# design.net
KiCad netlist of a schematic drawn in Altium Designer
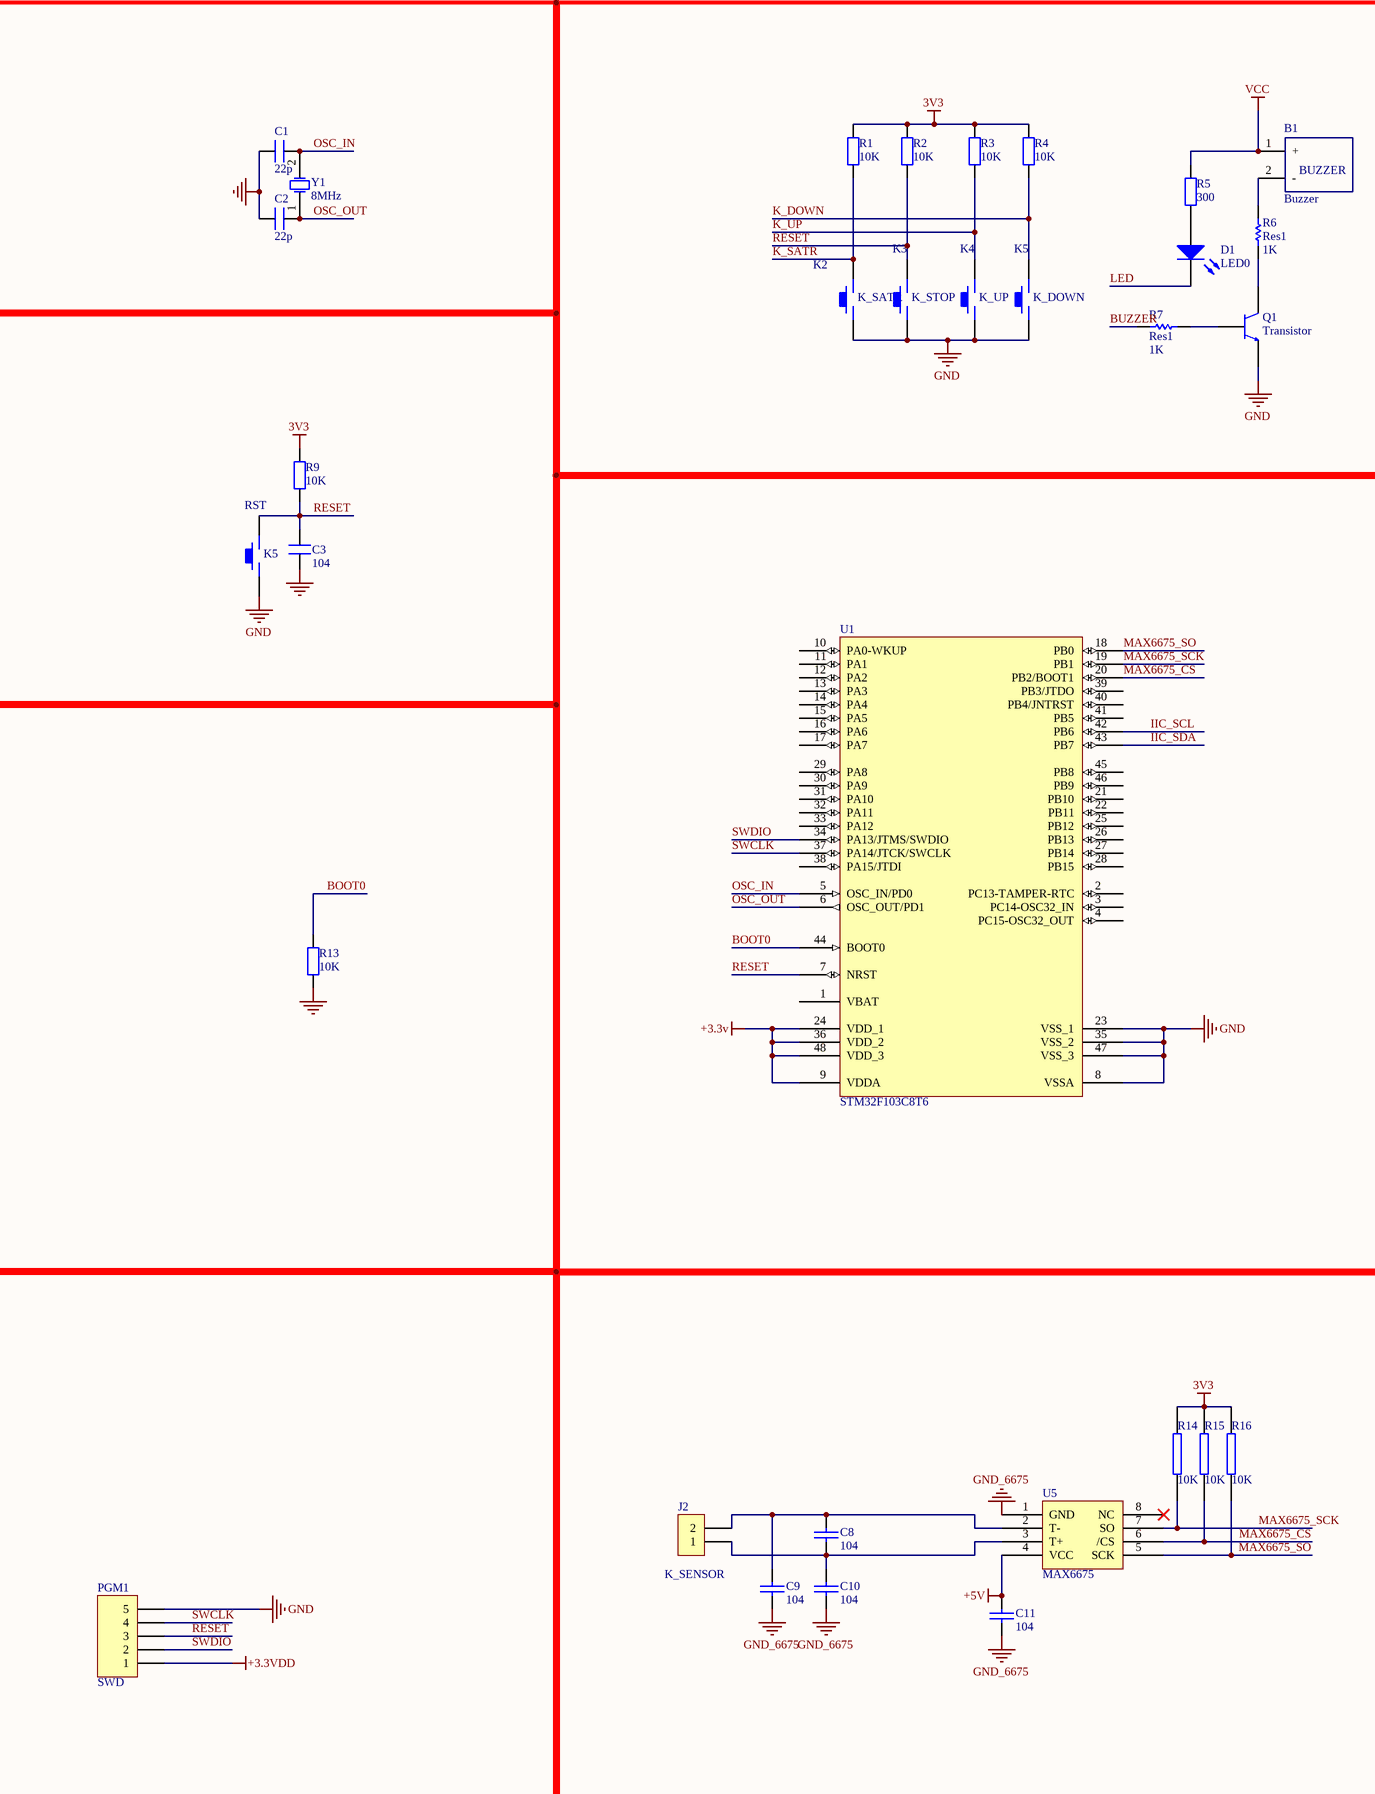
[diagram p0: 原理图.SchDoc, left]
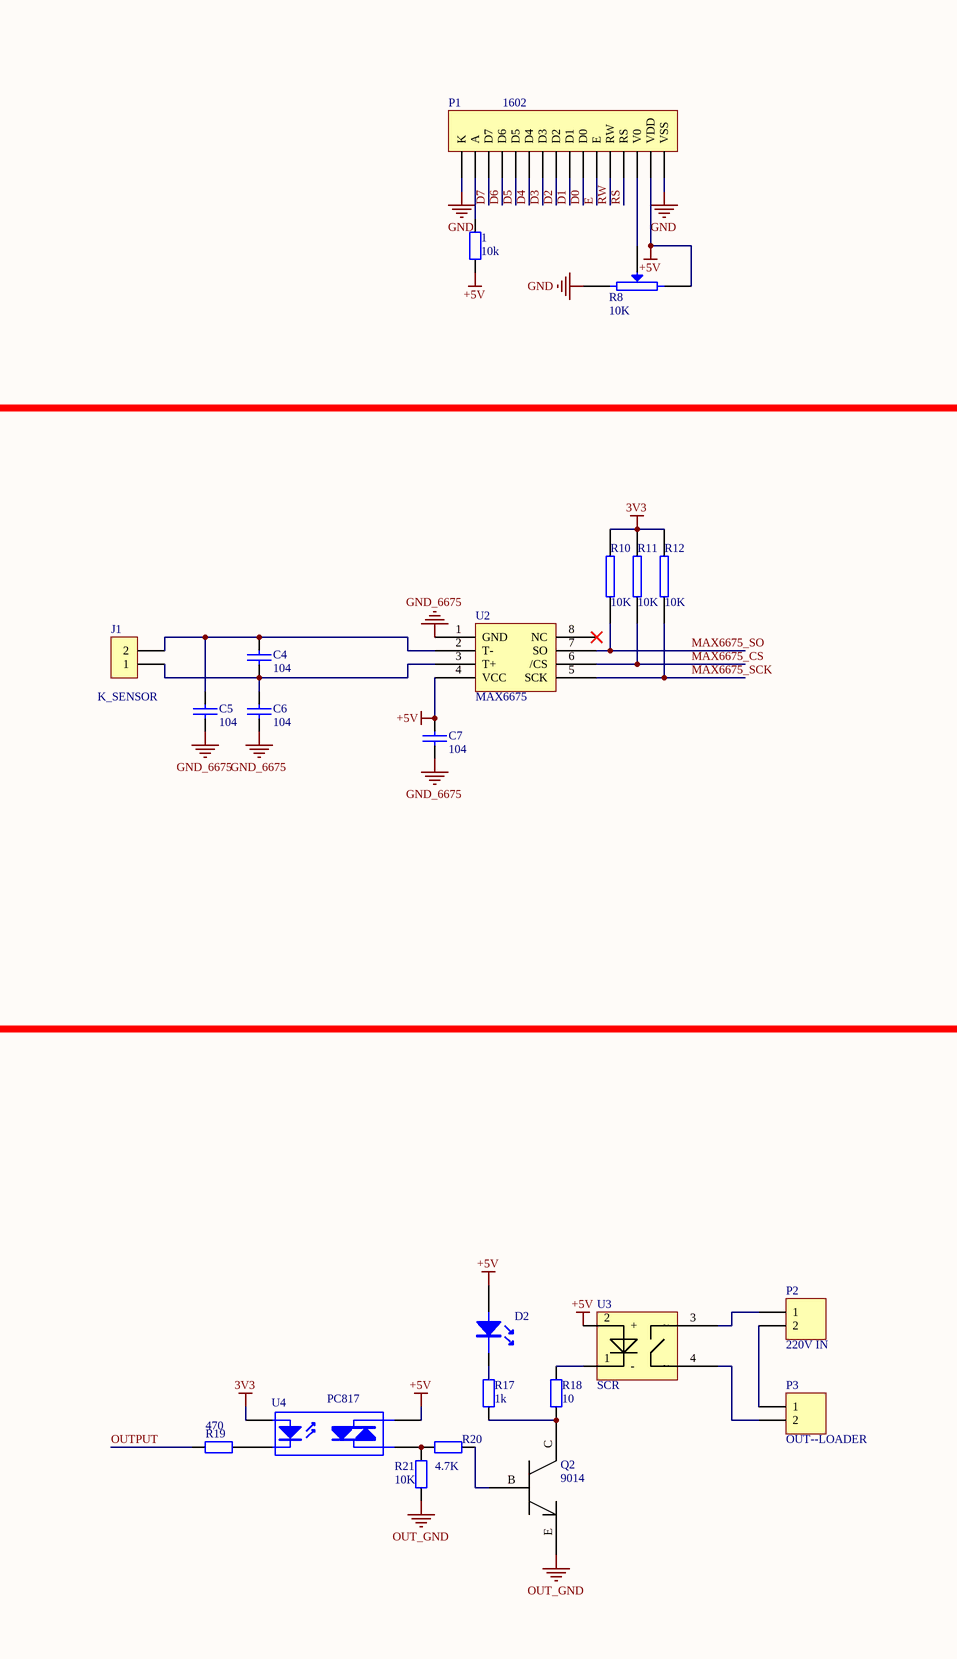
[diagram p1: 原理图.SchDoc, right]

(export (version "E")
  (design (tool "Eeschema 10.0.6"))
  (components
    (comp (ref "1")
      (value "10k")
      (footprint "AXIAL-0.4")
      (description "Resistor")
      (fields (field (name "PUBLISHER") "Altium Limited"))
      (libsource (lib "Miscellaneous Devices") (part "Res2"))
    )
    (comp (ref "B1") (value "Buzzer") (footprint "BUZZER") (libsource (lib "Second Version") (part "Buzzer")))
    (comp (ref "C1") (value "22p") (footprint "1206") (libsource (lib "MiniSTM32 V3.0封装库") (part "C")))
    (comp (ref "C2") (value "22p") (footprint "1206") (libsource (lib "MiniSTM32 V3.0封装库") (part "C")))
    (comp (ref "C3") (value "104") (footprint "1206") (libsource (lib "MiniSTM32 V3.0封装库") (part "C")))
    (comp (ref "C4")
      (value "104")
      (footprint "1206")
      (description "Capacitor")
      (libsource (lib "电容") (part "普通电容"))
    )
    (comp (ref "C5")
      (value "104")
      (footprint "1206")
      (description "Capacitor")
      (libsource (lib "电容") (part "普通电容"))
    )
    (comp (ref "C6")
      (value "104")
      (footprint "1206")
      (description "Capacitor")
      (libsource (lib "电容") (part "普通电容"))
    )
    (comp (ref "C7")
      (value "104")
      (footprint "1206")
      (description "Capacitor")
      (libsource (lib "电容") (part "普通电容"))
    )
    (comp (ref "C8")
      (value "104")
      (footprint "1206")
      (description "Capacitor")
      (libsource (lib "电容") (part "普通电容"))
    )
    (comp (ref "C9")
      (value "104")
      (footprint "1206")
      (description "Capacitor")
      (libsource (lib "电容") (part "普通电容"))
    )
    (comp (ref "C10")
      (value "104")
      (footprint "1206")
      (description "Capacitor")
      (libsource (lib "电容") (part "普通电容"))
    )
    (comp (ref "C11")
      (value "104")
      (footprint "1206")
      (description "Capacitor")
      (libsource (lib "电容") (part "普通电容"))
    )
    (comp (ref "D1")
      (value "LED0")
      (footprint "LED-0")
      (description "Typical INFRARED GaAs LED")
      (fields (field (name "PUBLISHER") "Altium Limited"))
      (libsource (lib "Miscellaneous Devices") (part "LED0"))
    )
    (comp (ref "D2") (value "~") (footprint "李建国1:LED") (libsource (lib "二极管") (part "发光二极管")))
    (comp (ref "J1")
      (value "K_SENSOR")
      (footprint "OUT_CJ")
      (description "Connector")
      (libsource (lib "Miscellaneous Devices") (part "CON2"))
    )
    (comp (ref "J2")
      (value "K_SENSOR")
      (footprint "OUT_CJ")
      (description "Connector")
      (libsource (lib "Miscellaneous Devices") (part "CON2"))
    )
    (comp (ref "K5") (value "RST") (footprint "KEY_M") (libsource (lib "底板封装库") (part "KEY_M")))
    (comp (ref "K_DOWN") (value "K5") (footprint "KEY_M") (libsource (lib "底板封装库") (part "KEY_M")))
    (comp (ref "K_SATR") (value "K2") (footprint "KEY_M") (libsource (lib "底板封装库") (part "KEY_M")))
    (comp (ref "K_STOP") (value "K3") (footprint "KEY_M") (libsource (lib "底板封装库") (part "KEY_M")))
    (comp (ref "K_UP") (value "K4") (footprint "KEY_M") (libsource (lib "底板封装库") (part "KEY_M")))
    (comp (ref "P1")
      (value "1602")
      (footprint "HDR1X16")
      (description "Header, 16-Pin")
      (fields (field (name "PUBLISHER") "Altium Limited"))
      (libsource (lib "Miscellaneous Connectors") (part "Header 16"))
    )
    (comp (ref "P2")
      (value "220V IN")
      (footprint "OUT_CJ")
      (description "Header, 2-Pin")
      (fields (field (name "PUBLISHER") "Altium Limited"))
      (libsource (lib "Miscellaneous Connectors") (part "Header 2"))
    )
    (comp (ref "P3")
      (value "OUT--LOADER")
      (footprint "OUT_CJ")
      (description "Header, 2-Pin")
      (fields (field (name "PUBLISHER") "Altium Limited"))
      (libsource (lib "Miscellaneous Connectors") (part "Header 2"))
    )
    (comp (ref "PGM1")
      (value "SWD")
      (footprint "HX2.54-5p")
      (description "Header, 5-Pin")
      (fields (field (name "PUBLISHER") "Altium Limited"))
      (libsource (lib "Miscellaneous Connectors") (part "Header 5"))
    )
    (comp (ref "Q1")
      (value "Transistor")
      (footprint "SOT23_TR")
      (libsource (lib "First Version") (part "NPN_Transistor_SOT23"))
    )
    (comp (ref "Q2") (value "9014") (footprint "9014") (libsource (lib "陈志伟2") (part "9014")))
    (comp (ref "R1")
      (value "10K")
      (footprint "1206")
      (description "Resistor")
      (fields (field (name "PUBLISHER") "Altium Limited"))
      (libsource (lib "") (part "Res2_2"))
    )
    (comp (ref "R2")
      (value "10K")
      (footprint "1206")
      (description "Resistor")
      (fields (field (name "PUBLISHER") "Altium Limited"))
      (libsource (lib "") (part "Res2_2"))
    )
    (comp (ref "R3")
      (value "10K")
      (footprint "1206")
      (description "Resistor")
      (fields (field (name "PUBLISHER") "Altium Limited"))
      (libsource (lib "") (part "Res2_2"))
    )
    (comp (ref "R4")
      (value "10K")
      (footprint "1206")
      (description "Resistor")
      (fields (field (name "PUBLISHER") "Altium Limited"))
      (libsource (lib "") (part "Res2_2"))
    )
    (comp (ref "R5")
      (value "300")
      (footprint "AXIAL-0.4")
      (description "Resistor")
      (fields (field (name "PUBLISHER") "Altium Limited"))
      (libsource (lib "Miscellaneous Devices") (part "Res2"))
    )
    (comp (ref "R6")
      (value "Res1")
      (footprint "SMD0805_RES")
      (description "Resistor")
      (fields (field (name "ALTIUM_VALUE") "1K") (field (name "PUBLISHER") "Altium Limited"))
      (libsource (lib "Miscellaneous Devices") (part "Res1"))
    )
    (comp (ref "R7")
      (value "Res1")
      (footprint "SMD0805_RES")
      (description "Resistor")
      (fields (field (name "ALTIUM_VALUE") "1K") (field (name "PUBLISHER") "Altium Limited"))
      (libsource (lib "Miscellaneous Devices") (part "Res1"))
    )
    (comp (ref "R8")
      (value "10K")
      (footprint "VR")
      (description "Potentiometer")
      (libsource (lib "电阻") (part "RESVR"))
    )
    (comp (ref "R9")
      (value "10K")
      (footprint "1206")
      (description "Resistor")
      (fields (field (name "PUBLISHER") "Altium Limited"))
      (libsource (lib "") (part "Res2_1"))
    )
    (comp (ref "R10") (value "10K") (footprint "1206") (libsource (lib "*") (part "RES2")))
    (comp (ref "R11") (value "10K") (footprint "1206") (libsource (lib "*") (part "RES2")))
    (comp (ref "R12") (value "10K") (footprint "1206") (libsource (lib "*") (part "RES2")))
    (comp (ref "R13")
      (value "10K")
      (footprint "1206")
      (description "Resistor")
      (fields (field (name "PUBLISHER") "Altium Limited"))
      (libsource (lib "") (part "Res2_1"))
    )
    (comp (ref "R14") (value "10K") (footprint "1206") (libsource (lib "*") (part "RES2")))
    (comp (ref "R15") (value "10K") (footprint "1206") (libsource (lib "*") (part "RES2")))
    (comp (ref "R16") (value "10K") (footprint "1206") (libsource (lib "*") (part "RES2")))
    (comp (ref "R17")
      (value "1k")
      (footprint "1206")
      (description "Resistor")
      (fields (field (name "PUBLISHER") "Altium Limited"))
      (libsource (lib "") (part "Res2_2"))
    )
    (comp (ref "R18")
      (value "10")
      (footprint "1206")
      (description "Resistor")
      (fields (field (name "PUBLISHER") "Altium Limited"))
      (libsource (lib "") (part "Res2_2"))
    )
    (comp (ref "R19")
      (value "470")
      (footprint "1206")
      (description "Resistor")
      (fields (field (name "PUBLISHER") "Altium Limited"))
      (libsource (lib "") (part "Res2_1"))
    )
    (comp (ref "R20")
      (value "4.7K")
      (footprint "1206")
      (description "Resistor")
      (fields (field (name "PUBLISHER") "Altium Limited"))
      (libsource (lib "") (part "Res2_1"))
    )
    (comp (ref "R21")
      (value "10K")
      (footprint "1206")
      (description "Resistor")
      (fields (field (name "PUBLISHER") "Altium Limited"))
      (libsource (lib "") (part "Res2_2"))
    )
    (comp (ref "U1")
      (value "STM32F103C8T6")
      (footprint "LQFP48_N")
      (description "STM32 ARM-based 32-bit MCU with 64 Kbytes Flash, 48-pin LQFP, Industrial Temperature")
      (fields (field (name "PUBLISHER") "Altium Limited"))
      (libsource (lib "ST Microcontroller 32-Bit STM32") (part "STM32F103C8T6"))
    )
    (comp (ref "U2") (value "MAX6675") (footprint "SO-8") (libsource (lib "温控库") (part "MAX6675")))
    (comp (ref "U3") (value "SCR") (footprint "SCR") (libsource (lib "*") (part "SCR")))
    (comp (ref "U4")
      (value "PC817")
      (footprint "pc817")
      (libsource (lib "Miscellaneous Devices") (part "OPTOTRIAC"))
    )
    (comp (ref "U5") (value "MAX6675") (footprint "SO-8") (libsource (lib "温控库") (part "MAX6675")))
    (comp (ref "Y1")
      (value "8MHz")
      (footprint "XTAL_US")
      (description "Crystal Oscillator")
      (fields (field (name "PUBLISHER") "Altium Limited"))
      (libsource (lib "MiniSTM32 V3.0封装库") (part "XTAL"))
    )
  )
  (nets
    (net (code "1") (name "+3.3VDD") (class "Default")
      (node (ref "PGM1") (pin "1") (pinfunction "1_1") (pintype "passive"))
    )
    (net (code "2") (name "+3.3v") (class "Default")
      (node (ref "U1") (pin "24") (pinfunction "VDD_1_24") (pintype "power_in"))
      (node (ref "U1") (pin "36") (pinfunction "VDD_2_36") (pintype "power_in"))
      (node (ref "U1") (pin "48") (pinfunction "VDD_3_48") (pintype "power_in"))
      (node (ref "U1") (pin "9") (pinfunction "VDDA_9") (pintype "power_in"))
    )
    (net (code "3") (name "+5V") (class "Default")
      (node (ref "1") (pin "1") (pinfunction "1_1") (pintype "passive"))
      (node (ref "C11") (pin "1") (pinfunction "1_1") (pintype "passive"))
      (node (ref "C7") (pin "1") (pinfunction "1_1") (pintype "passive"))
      (node (ref "D2") (pin "A") (pinfunction "1_A") (pintype "passive"))
      (node (ref "P1") (pin "2") (pinfunction "VDD_2") (pintype "passive"))
      (node (ref "R8") (pin "2") (pinfunction "2_2") (pintype "passive"))
      (node (ref "U2") (pin "4") (pinfunction "VCC_4") (pintype "passive"))
      (node (ref "U3") (pin "2") (pinfunction "+_2") (pintype "passive"))
      (node (ref "U4") (pin "3") (pinfunction "A/K_3") (pintype "passive"))
      (node (ref "U5") (pin "4") (pinfunction "VCC_4") (pintype "passive"))
    )
    (net (code "4") (name "/BOOT0") (class "Default")
      (node (ref "R13") (pin "1") (pinfunction "1_1") (pintype "passive"))
      (node (ref "U1") (pin "44") (pinfunction "BOOT0_44") (pintype "input"))
    )
    (net (code "5") (name "/BUZZER") (class "Default")
      (node (ref "R7") (pin "1") (pinfunction "1_1") (pintype "passive"))
    )
    (net (code "6") (name "/D0") (class "Default")
      (node (ref "P1") (pin "7") (pinfunction "D0_7") (pintype "passive"))
    )
    (net (code "7") (name "/D1") (class "Default")
      (node (ref "P1") (pin "8") (pinfunction "D1_8") (pintype "passive"))
    )
    (net (code "8") (name "/D2") (class "Default")
      (node (ref "P1") (pin "9") (pinfunction "D2_9") (pintype "passive"))
    )
    (net (code "9") (name "/D3") (class "Default")
      (node (ref "P1") (pin "10") (pinfunction "D3_10") (pintype "passive"))
    )
    (net (code "10") (name "/D4") (class "Default")
      (node (ref "P1") (pin "11") (pinfunction "D4_11") (pintype "passive"))
    )
    (net (code "11") (name "/D5") (class "Default")
      (node (ref "P1") (pin "12") (pinfunction "D5_12") (pintype "passive"))
    )
    (net (code "12") (name "/D6") (class "Default")
      (node (ref "P1") (pin "13") (pinfunction "D6_13") (pintype "passive"))
    )
    (net (code "13") (name "/D7") (class "Default")
      (node (ref "P1") (pin "14") (pinfunction "D7_14") (pintype "passive"))
    )
    (net (code "14") (name "/E") (class "Default")
      (node (ref "P1") (pin "6") (pinfunction "E_6") (pintype "passive"))
    )
    (net (code "15") (name "/IIC_SCL") (class "Default")
      (node (ref "U1") (pin "42") (pinfunction "PB6_42") (pintype "bidirectional"))
    )
    (net (code "16") (name "/IIC_SDA") (class "Default")
      (node (ref "U1") (pin "43") (pinfunction "PB7_43") (pintype "bidirectional"))
    )
    (net (code "17") (name "/K_DOWN") (class "Default")
      (node (ref "K_DOWN") (pin "2") (pinfunction "2_2") (pintype "passive"))
      (node (ref "R4") (pin "1") (pinfunction "1_1") (pintype "passive"))
    )
    (net (code "18") (name "/K_SATR") (class "Default")
      (node (ref "K_SATR") (pin "2") (pinfunction "2_2") (pintype "passive"))
      (node (ref "R1") (pin "1") (pinfunction "1_1") (pintype "passive"))
    )
    (net (code "19") (name "/K_UP") (class "Default")
      (node (ref "K_UP") (pin "2") (pinfunction "2_2") (pintype "passive"))
      (node (ref "R3") (pin "1") (pinfunction "1_1") (pintype "passive"))
    )
    (net (code "20") (name "/LED") (class "Default")
      (node (ref "D1") (pin "2") (pinfunction "K_2") (pintype "passive"))
    )
    (net (code "21") (name "/MAX6675_CS") (class "Default")
      (node (ref "R11") (pin "1") (pinfunction "1_1") (pintype "passive"))
      (node (ref "R15") (pin "1") (pinfunction "1_1") (pintype "passive"))
      (node (ref "U1") (pin "20") (pinfunction "PB2/BOOT1_20") (pintype "bidirectional"))
      (node (ref "U2") (pin "6") (pinfunction "/CS_6") (pintype "passive"))
      (node (ref "U5") (pin "6") (pinfunction "/CS_6") (pintype "passive"))
    )
    (net (code "22") (name "/MAX6675_SCK") (class "Default")
      (node (ref "R12") (pin "1") (pinfunction "1_1") (pintype "passive"))
      (node (ref "R14") (pin "1") (pinfunction "1_1") (pintype "passive"))
      (node (ref "U1") (pin "19") (pinfunction "PB1_19") (pintype "bidirectional"))
      (node (ref "U2") (pin "5") (pinfunction "SCK_5") (pintype "passive"))
      (node (ref "U5") (pin "7") (pinfunction "SO_7") (pintype "passive"))
    )
    (net (code "23") (name "/MAX6675_SO") (class "Default")
      (node (ref "R10") (pin "1") (pinfunction "1_1") (pintype "passive"))
      (node (ref "R16") (pin "1") (pinfunction "1_1") (pintype "passive"))
      (node (ref "U1") (pin "18") (pinfunction "PB0_18") (pintype "bidirectional"))
      (node (ref "U2") (pin "7") (pinfunction "SO_7") (pintype "passive"))
      (node (ref "U5") (pin "5") (pinfunction "SCK_5") (pintype "passive"))
    )
    (net (code "24") (name "/OSC_IN") (class "Default")
      (node (ref "C1") (pin "1") (pintype "passive"))
      (node (ref "U1") (pin "5") (pinfunction "OSC_IN/PD0_5") (pintype "input"))
      (node (ref "Y1") (pin "2") (pinfunction "OSC2_2") (pintype "passive"))
    )
    (net (code "25") (name "/OSC_OUT") (class "Default")
      (node (ref "C2") (pin "2") (pintype "passive"))
      (node (ref "U1") (pin "6") (pinfunction "OSC_OUT/PD1_6") (pintype "output"))
      (node (ref "Y1") (pin "1") (pinfunction "OSC1_1") (pintype "passive"))
    )
    (net (code "26") (name "/OUTPUT") (class "Default")
      (node (ref "R19") (pin "2") (pinfunction "2_2") (pintype "passive"))
    )
    (net (code "27") (name "/RESET") (class "Default")
      (node (ref "C3") (pin "1") (pintype "passive"))
      (node (ref "K5") (pin "2") (pinfunction "2_2") (pintype "passive"))
      (node (ref "K_STOP") (pin "2") (pinfunction "2_2") (pintype "passive"))
      (node (ref "PGM1") (pin "3") (pinfunction "3_3") (pintype "passive"))
      (node (ref "R2") (pin "1") (pinfunction "1_1") (pintype "passive"))
      (node (ref "R9") (pin "2") (pinfunction "2_2") (pintype "passive"))
      (node (ref "U1") (pin "7") (pinfunction "NRST_7") (pintype "bidirectional"))
    )
    (net (code "28") (name "/RS") (class "Default")
      (node (ref "P1") (pin "4") (pinfunction "RS_4") (pintype "passive"))
    )
    (net (code "29") (name "/RW") (class "Default")
      (node (ref "P1") (pin "5") (pinfunction "RW_5") (pintype "passive"))
    )
    (net (code "30") (name "/SWCLK") (class "Default")
      (node (ref "PGM1") (pin "4") (pinfunction "4_4") (pintype "passive"))
      (node (ref "U1") (pin "37") (pinfunction "PA14/JTCK/SWCLK_37") (pintype "bidirectional"))
    )
    (net (code "31") (name "/SWDIO") (class "Default")
      (node (ref "PGM1") (pin "2") (pinfunction "2_2") (pintype "passive"))
      (node (ref "U1") (pin "34") (pinfunction "PA13/JTMS/SWDIO_34") (pintype "bidirectional"))
    )
    (net (code "32") (name "3V3") (class "Default")
      (node (ref "R1") (pin "2") (pinfunction "2_2") (pintype "passive"))
      (node (ref "R10") (pin "2") (pinfunction "2_2") (pintype "passive"))
      (node (ref "R11") (pin "2") (pinfunction "2_2") (pintype "passive"))
      (node (ref "R12") (pin "2") (pinfunction "2_2") (pintype "passive"))
      (node (ref "R14") (pin "2") (pinfunction "2_2") (pintype "passive"))
      (node (ref "R15") (pin "2") (pinfunction "2_2") (pintype "passive"))
      (node (ref "R16") (pin "2") (pinfunction "2_2") (pintype "passive"))
      (node (ref "R2") (pin "2") (pinfunction "2_2") (pintype "passive"))
      (node (ref "R3") (pin "2") (pinfunction "2_2") (pintype "passive"))
      (node (ref "R4") (pin "2") (pinfunction "2_2") (pintype "passive"))
      (node (ref "R9") (pin "1") (pinfunction "1_1") (pintype "passive"))
      (node (ref "U4") (pin "1") (pinfunction "A_1") (pintype "passive"))
    )
    (net (code "33") (name "GND") (class "Default")
      (node (ref "C1") (pin "2") (pintype "passive"))
      (node (ref "C2") (pin "1") (pintype "passive"))
      (node (ref "C3") (pin "2") (pintype "passive"))
      (node (ref "K5") (pin "1") (pinfunction "1_1") (pintype "passive"))
      (node (ref "K_DOWN") (pin "1") (pinfunction "1_1") (pintype "passive"))
      (node (ref "K_SATR") (pin "1") (pinfunction "1_1") (pintype "passive"))
      (node (ref "K_STOP") (pin "1") (pinfunction "1_1") (pintype "passive"))
      (node (ref "K_UP") (pin "1") (pinfunction "1_1") (pintype "passive"))
      (node (ref "P1") (pin "1") (pinfunction "VSS_1") (pintype "passive"))
      (node (ref "P1") (pin "16") (pinfunction "K_16") (pintype "passive"))
      (node (ref "PGM1") (pin "5") (pinfunction "5_5") (pintype "passive"))
      (node (ref "Q1") (pin "2") (pinfunction "2_2") (pintype "passive"))
      (node (ref "R13") (pin "2") (pinfunction "2_2") (pintype "passive"))
      (node (ref "R8") (pin "1") (pinfunction "1_1") (pintype "passive"))
      (node (ref "U1") (pin "23") (pinfunction "VSS_1_23") (pintype "power_in"))
      (node (ref "U1") (pin "35") (pinfunction "VSS_2_35") (pintype "power_in"))
      (node (ref "U1") (pin "47") (pinfunction "VSS_3_47") (pintype "power_in"))
      (node (ref "U1") (pin "8") (pinfunction "VSSA_8") (pintype "power_in"))
    )
    (net (code "34") (name "GND_6675") (class "Default")
      (node (ref "C10") (pin "2") (pinfunction "2_2") (pintype "passive"))
      (node (ref "C11") (pin "2") (pinfunction "2_2") (pintype "passive"))
      (node (ref "C5") (pin "2") (pinfunction "2_2") (pintype "passive"))
      (node (ref "C6") (pin "2") (pinfunction "2_2") (pintype "passive"))
      (node (ref "C7") (pin "2") (pinfunction "2_2") (pintype "passive"))
      (node (ref "C9") (pin "2") (pinfunction "2_2") (pintype "passive"))
      (node (ref "U2") (pin "1") (pinfunction "GND_1") (pintype "passive"))
      (node (ref "U5") (pin "1") (pinfunction "GND_1") (pintype "passive"))
    )
    (net (code "35") (name "Net-(B1--)") (class "Default")
      (node (ref "B1") (pin "2") (pinfunction "-_2") (pintype "passive"))
      (node (ref "R6") (pin "2") (pinfunction "2_2") (pintype "passive"))
    )
    (net (code "36") (name "Net-(D1-A)") (class "Default")
      (node (ref "D1") (pin "1") (pinfunction "A_1") (pintype "passive"))
      (node (ref "R5") (pin "1") (pinfunction "1_1") (pintype "passive"))
    )
    (net (code "37") (name "Net-(D2-2)") (class "Default")
      (node (ref "D2") (pin "K") (pinfunction "2_K") (pintype "passive"))
      (node (ref "R17") (pin "2") (pinfunction "2_2") (pintype "passive"))
    )
    (net (code "38") (name "Net-(P1-A)") (class "Default")
      (node (ref "1") (pin "2") (pinfunction "2_2") (pintype "passive"))
      (node (ref "P1") (pin "15") (pinfunction "A_15") (pintype "passive"))
    )
    (net (code "39") (name "Net-(P1-V0)") (class "Default")
      (node (ref "P1") (pin "3") (pinfunction "V0_3") (pintype "passive"))
      (node (ref "R8") (pin "3") (pinfunction "W_3") (pintype "passive"))
    )
    (net (code "40") (name "Net-(P2-Pad1)") (class "Default")
      (node (ref "P2") (pin "1") (pinfunction "1_1") (pintype "passive"))
      (node (ref "U3") (pin "3") (pinfunction "~_3") (pintype "passive"))
    )
    (net (code "41") (name "Net-(P2-Pad2)") (class "Default")
      (node (ref "P2") (pin "2") (pinfunction "2_2") (pintype "passive"))
      (node (ref "P3") (pin "1") (pinfunction "1_1") (pintype "passive"))
    )
    (net (code "42") (name "Net-(P3-Pad2)") (class "Default")
      (node (ref "P3") (pin "2") (pinfunction "2_2") (pintype "passive"))
      (node (ref "U3") (pin "4") (pinfunction "~_4") (pintype "passive"))
    )
    (net (code "43") (name "Net-(Q1-Pad1)") (class "Default")
      (node (ref "Q1") (pin "1") (pinfunction "1_1") (pintype "passive"))
      (node (ref "R7") (pin "2") (pinfunction "2_2") (pintype "passive"))
    )
    (net (code "44") (name "Net-(Q1-Pad3)") (class "Default")
      (node (ref "Q1") (pin "3") (pinfunction "3_3") (pintype "passive"))
      (node (ref "R6") (pin "1") (pinfunction "1_1") (pintype "passive"))
    )
    (net (code "45") (name "Net-(Q2-PadB)") (class "Default")
      (node (ref "Q2") (pin "B") (pinfunction "B_B") (pintype "passive"))
      (node (ref "R20") (pin "1") (pinfunction "1_1") (pintype "passive"))
    )
    (net (code "46") (name "Net-(Q2-PadC)") (class "Default")
      (node (ref "Q2") (pin "C") (pinfunction "C_C") (pintype "passive"))
      (node (ref "R17") (pin "1") (pinfunction "1_1") (pintype "passive"))
      (node (ref "R18") (pin "1") (pinfunction "1_1") (pintype "passive"))
    )
    (net (code "47") (name "Net-(R20-Pad2)") (class "Default")
      (node (ref "R20") (pin "2") (pinfunction "2_2") (pintype "passive"))
      (node (ref "R21") (pin "2") (pinfunction "2_2") (pintype "passive"))
      (node (ref "U4") (pin "4") (pinfunction "A/K_4") (pintype "passive"))
    )
    (net (code "48") (name "Net-(U2-T+)") (class "Default")
      (node (ref "C4") (pin "2") (pinfunction "2_2") (pintype "passive"))
      (node (ref "C6") (pin "1") (pinfunction "1_1") (pintype "passive"))
      (node (ref "J1") (pin "1") (pinfunction "1_1") (pintype "passive"))
      (node (ref "U2") (pin "3") (pinfunction "T+_3") (pintype "passive"))
    )
    (net (code "49") (name "Net-(U2-T-)") (class "Default")
      (node (ref "C4") (pin "1") (pinfunction "1_1") (pintype "passive"))
      (node (ref "C5") (pin "1") (pinfunction "1_1") (pintype "passive"))
      (node (ref "J1") (pin "2") (pinfunction "2_2") (pintype "passive"))
      (node (ref "U2") (pin "2") (pinfunction "T-_2") (pintype "passive"))
    )
    (net (code "50") (name "Net-(U3--)") (class "Default")
      (node (ref "R18") (pin "2") (pinfunction "2_2") (pintype "passive"))
      (node (ref "U3") (pin "1") (pinfunction "-_1") (pintype "passive"))
    )
    (net (code "51") (name "Net-(U4-K)") (class "Default")
      (node (ref "R19") (pin "1") (pinfunction "1_1") (pintype "passive"))
      (node (ref "U4") (pin "2") (pinfunction "K_2") (pintype "passive"))
    )
    (net (code "52") (name "Net-(U5-T+)") (class "Default")
      (node (ref "C10") (pin "1") (pinfunction "1_1") (pintype "passive"))
      (node (ref "C8") (pin "2") (pinfunction "2_2") (pintype "passive"))
      (node (ref "J2") (pin "1") (pinfunction "1_1") (pintype "passive"))
      (node (ref "U5") (pin "3") (pinfunction "T+_3") (pintype "passive"))
    )
    (net (code "53") (name "Net-(U5-T-)") (class "Default")
      (node (ref "C8") (pin "1") (pinfunction "1_1") (pintype "passive"))
      (node (ref "C9") (pin "1") (pinfunction "1_1") (pintype "passive"))
      (node (ref "J2") (pin "2") (pinfunction "2_2") (pintype "passive"))
      (node (ref "U5") (pin "2") (pinfunction "T-_2") (pintype "passive"))
    )
    (net (code "54") (name "OUT_GND") (class "Default")
      (node (ref "Q2") (pin "E") (pinfunction "E_E") (pintype "passive"))
      (node (ref "R21") (pin "1") (pinfunction "1_1") (pintype "passive"))
    )
    (net (code "55") (name "VCC") (class "Default")
      (node (ref "B1") (pin "1") (pinfunction "+_1") (pintype "passive"))
      (node (ref "R5") (pin "2") (pinfunction "2_2") (pintype "passive"))
    )
    (net (code "56") (name "unconnected-(U1-PA0-WKUP-Pad10)") (class "Default")
      (node (ref "U1") (pin "10") (pinfunction "PA0-WKUP_10") (pintype "bidirectional"))
    )
    (net (code "57") (name "unconnected-(U1-PA1-Pad11)") (class "Default")
      (node (ref "U1") (pin "11") (pinfunction "PA1_11") (pintype "bidirectional"))
    )
    (net (code "58") (name "unconnected-(U1-PA2-Pad12)") (class "Default")
      (node (ref "U1") (pin "12") (pinfunction "PA2_12") (pintype "bidirectional"))
    )
    (net (code "59") (name "unconnected-(U1-PA3-Pad13)") (class "Default")
      (node (ref "U1") (pin "13") (pinfunction "PA3_13") (pintype "bidirectional"))
    )
    (net (code "60") (name "unconnected-(U1-PA4-Pad14)") (class "Default")
      (node (ref "U1") (pin "14") (pinfunction "PA4_14") (pintype "bidirectional"))
    )
    (net (code "61") (name "unconnected-(U1-PA5-Pad15)") (class "Default")
      (node (ref "U1") (pin "15") (pinfunction "PA5_15") (pintype "bidirectional"))
    )
    (net (code "62") (name "unconnected-(U1-PA6-Pad16)") (class "Default")
      (node (ref "U1") (pin "16") (pinfunction "PA6_16") (pintype "bidirectional"))
    )
    (net (code "63") (name "unconnected-(U1-PA7-Pad17)") (class "Default")
      (node (ref "U1") (pin "17") (pinfunction "PA7_17") (pintype "bidirectional"))
    )
    (net (code "64") (name "unconnected-(U1-PA8-Pad29)") (class "Default")
      (node (ref "U1") (pin "29") (pinfunction "PA8_29") (pintype "bidirectional"))
    )
    (net (code "65") (name "unconnected-(U1-PA9-Pad30)") (class "Default")
      (node (ref "U1") (pin "30") (pinfunction "PA9_30") (pintype "bidirectional"))
    )
    (net (code "66") (name "unconnected-(U1-PA10-Pad31)") (class "Default")
      (node (ref "U1") (pin "31") (pinfunction "PA10_31") (pintype "bidirectional"))
    )
    (net (code "67") (name "unconnected-(U1-PA11-Pad32)") (class "Default")
      (node (ref "U1") (pin "32") (pinfunction "PA11_32") (pintype "bidirectional"))
    )
    (net (code "68") (name "unconnected-(U1-PA12-Pad33)") (class "Default")
      (node (ref "U1") (pin "33") (pinfunction "PA12_33") (pintype "bidirectional"))
    )
    (net (code "69") (name "unconnected-(U1-PA15{slash}JTDI-Pad38)") (class "Default")
      (node (ref "U1") (pin "38") (pinfunction "PA15/JTDI_38") (pintype "bidirectional"))
    )
    (net (code "70") (name "unconnected-(U1-PB3{slash}JTDO-Pad39)") (class "Default")
      (node (ref "U1") (pin "39") (pinfunction "PB3/JTDO_39") (pintype "bidirectional"))
    )
    (net (code "71") (name "unconnected-(U1-PB4{slash}JNTRST-Pad40)") (class "Default")
      (node (ref "U1") (pin "40") (pinfunction "PB4/JNTRST_40") (pintype "bidirectional"))
    )
    (net (code "72") (name "unconnected-(U1-PB5-Pad41)") (class "Default")
      (node (ref "U1") (pin "41") (pinfunction "PB5_41") (pintype "bidirectional"))
    )
    (net (code "73") (name "unconnected-(U1-PB8-Pad45)") (class "Default")
      (node (ref "U1") (pin "45") (pinfunction "PB8_45") (pintype "bidirectional"))
    )
    (net (code "74") (name "unconnected-(U1-PB9-Pad46)") (class "Default")
      (node (ref "U1") (pin "46") (pinfunction "PB9_46") (pintype "bidirectional"))
    )
    (net (code "75") (name "unconnected-(U1-PB10-Pad21)") (class "Default")
      (node (ref "U1") (pin "21") (pinfunction "PB10_21") (pintype "bidirectional"))
    )
    (net (code "76") (name "unconnected-(U1-PB11-Pad22)") (class "Default")
      (node (ref "U1") (pin "22") (pinfunction "PB11_22") (pintype "bidirectional"))
    )
    (net (code "77") (name "unconnected-(U1-PB12-Pad25)") (class "Default")
      (node (ref "U1") (pin "25") (pinfunction "PB12_25") (pintype "bidirectional"))
    )
    (net (code "78") (name "unconnected-(U1-PB13-Pad26)") (class "Default")
      (node (ref "U1") (pin "26") (pinfunction "PB13_26") (pintype "bidirectional"))
    )
    (net (code "79") (name "unconnected-(U1-PB14-Pad27)") (class "Default")
      (node (ref "U1") (pin "27") (pinfunction "PB14_27") (pintype "bidirectional"))
    )
    (net (code "80") (name "unconnected-(U1-PB15-Pad28)") (class "Default")
      (node (ref "U1") (pin "28") (pinfunction "PB15_28") (pintype "bidirectional"))
    )
    (net (code "81") (name "unconnected-(U1-PC13-TAMPER-RTC-Pad2)") (class "Default")
      (node (ref "U1") (pin "2") (pinfunction "PC13-TAMPER-RTC_2") (pintype "bidirectional"))
    )
    (net (code "82") (name "unconnected-(U1-PC14-OSC32_IN-Pad3)") (class "Default")
      (node (ref "U1") (pin "3") (pinfunction "PC14-OSC32_IN_3") (pintype "bidirectional"))
    )
    (net (code "83") (name "unconnected-(U1-PC15-OSC32_OUT-Pad4)") (class "Default")
      (node (ref "U1") (pin "4") (pinfunction "PC15-OSC32_OUT_4") (pintype "bidirectional"))
    )
    (net (code "84") (name "unconnected-(U1-VBAT-Pad1)") (class "Default")
      (node (ref "U1") (pin "1") (pinfunction "VBAT_1") (pintype "power_in"))
    )
    (net (code "85") (name "unconnected-(U2-NC-Pad8)") (class "Default")
      (node (ref "U2") (pin "8") (pinfunction "NC_8") (pintype "passive+no_connect"))
    )
    (net (code "86") (name "unconnected-(U5-NC-Pad8)") (class "Default")
      (node (ref "U5") (pin "8") (pinfunction "NC_8") (pintype "passive+no_connect"))
    )
  )
)
